# Adafruit_PowerBoost_1000C_Rev_B.net
KiCad netlist of a schematic drawn in EAGLE
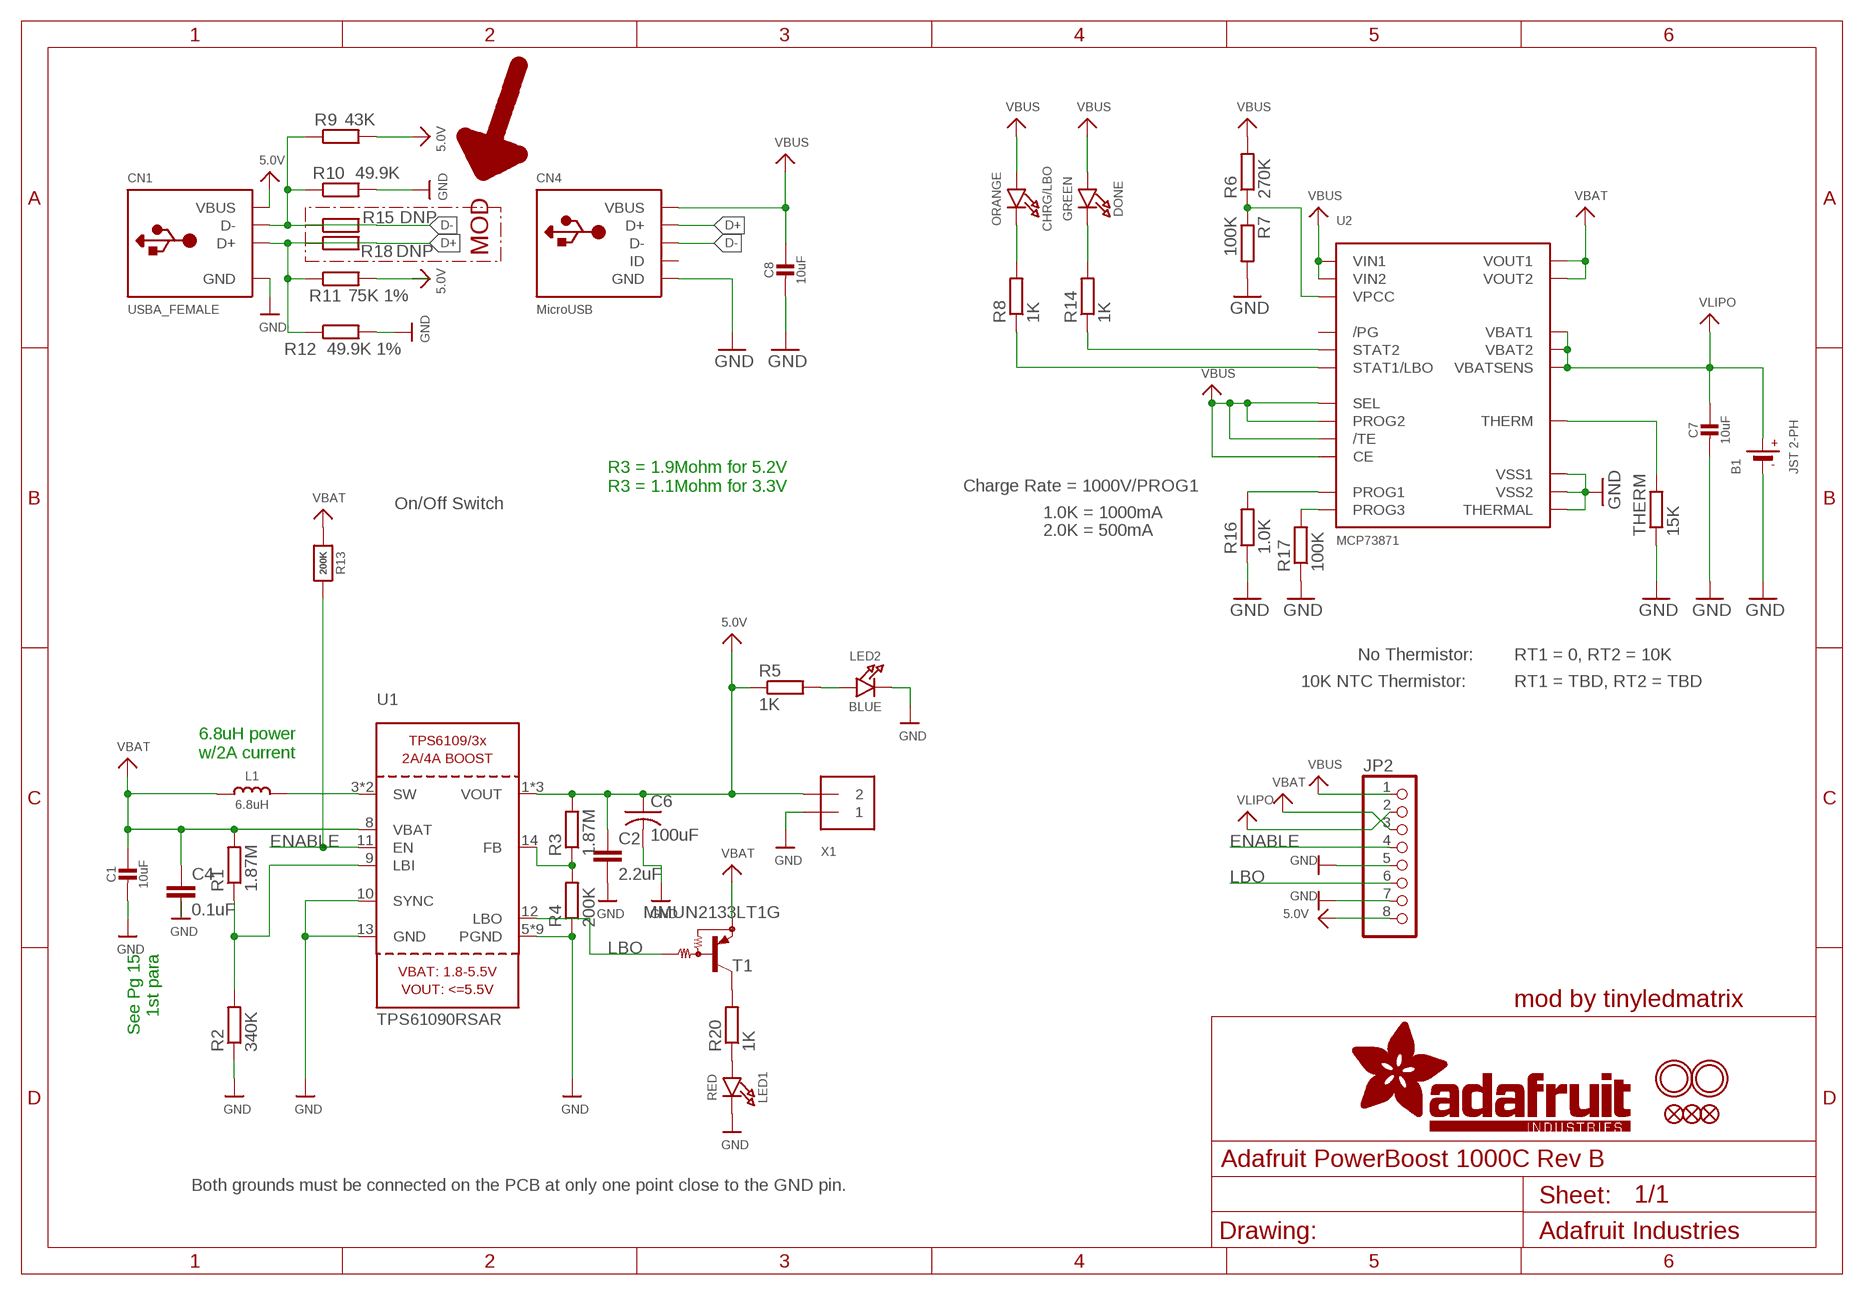
[diagram p0: schematic, sheet 1]

(export (version "E")
  (design (tool "Eeschema 10.0.6"))
  (components
    (comp (ref "B1")
      (value "JST 2-PH")
      (footprint "eagle-import:JSTPH2")
      (libsource (lib "eagle-import") (part "BATTERY"))
    )
    (comp (ref "C1")
      (value "10uF")
      (footprint "eagle-import:0805-NO")
      (libsource (lib "eagle-import") (part "CAP_CERAMIC0805-NOOUTLINE"))
    )
    (comp (ref "C2")
      (value "2.2uF")
      (footprint "eagle-import:C0603-VISHAY")
      (libsource (lib "eagle-import") (part "C-EUC0603-VISHAY"))
    )
    (comp (ref "C4")
      (value "0.1uF")
      (footprint "eagle-import:C0603-VISHAY")
      (libsource (lib "eagle-import") (part "C-EUC0603-VISHAY"))
    )
    (comp (ref "C6")
      (value "100uF")
      (footprint "eagle-import:C1210")
      (libsource (lib "eagle-import") (part "C-USC1210"))
    )
    (comp (ref "C7")
      (value "10uF")
      (footprint "eagle-import:0805-NO")
      (libsource (lib "eagle-import") (part "CAP_CERAMIC0805-NOOUTLINE"))
    )
    (comp (ref "C8")
      (value "10uF")
      (footprint "eagle-import:0805-NO")
      (libsource (lib "eagle-import") (part "CAP_CERAMIC0805-NOOUTLINE"))
    )
    (comp (ref "CHRG/LBO")
      (value "ORANGE")
      (footprint "eagle-import:CHIPLED_0603_NOOUTLINE")
      (libsource (lib "eagle-import") (part "LED0603_NOOUTLINE"))
    )
    (comp (ref "CN1")
      (value "USBA_FEMALE")
      (footprint "eagle-import:USB_HOST-PTH")
      (libsource (lib "eagle-import") (part "USB_TYPEAPTHFML"))
    )
    (comp (ref "CN4")
      (value "MicroUSB")
      (footprint "eagle-import:4UCONN_20329")
      (libsource (lib "eagle-import") (part "USBMICRO_20329"))
    )
    (comp (ref "DONE")
      (value "GREEN")
      (footprint "eagle-import:CHIPLED_0603_NOOUTLINE")
      (libsource (lib "eagle-import") (part "LED0603_NOOUTLINE"))
    )
    (comp (ref "FID1")
      (value "FIDUCIAL\"\"")
      (footprint "eagle-import:FIDUCIAL_1MM")
      (fields (field (name "BOM") "EXCLUDE"))
      (libsource (lib "eagle-import") (part "FIDUCIAL{dblquote}{dblquote}"))
    )
    (comp (ref "FID2")
      (value "FIDUCIAL\"\"")
      (footprint "eagle-import:FIDUCIAL_1MM")
      (libsource (lib "eagle-import") (part "FIDUCIAL{dblquote}{dblquote}"))
    )
    (comp (ref "FID3")
      (value "FIDUCIAL\"\"")
      (footprint "eagle-import:FIDUCIAL_1MM")
      (fields (field (name "BOM") "EXCLUDE"))
      (libsource (lib "eagle-import") (part "FIDUCIAL{dblquote}{dblquote}"))
    )
    (comp (ref "JP2")
      (value "HEADER-1X8ROUND")
      (footprint "eagle-import:1X08_ROUND")
      (libsource (lib "eagle-import") (part "HEADER-1X8ROUND"))
    )
    (comp (ref "L1")
      (value "6.8uH")
      (footprint "eagle-import:INDUCTOR_5X5MM_TDK_VLC5045")
      (libsource (lib "eagle-import") (part "INDUCTORTDK_VLC5045"))
    )
    (comp (ref "LED1")
      (value "RED")
      (footprint "eagle-import:CHIPLED_0603_NOOUTLINE")
      (libsource (lib "eagle-import") (part "LED0603_NOOUTLINE"))
    )
    (comp (ref "LED2")
      (value "BLUE")
      (footprint "eagle-import:CHIPLED_0603_NOOUTLINE")
      (libsource (lib "eagle-import") (part "LED0603_NOOUTLINE"))
    )
    (comp (ref "R1")
      (value "1.87M")
      (footprint "eagle-import:ADAFRUIT_R0603-VISHAY")
      (libsource (lib "eagle-import") (part "R-EU_R0603-VISHAY"))
    )
    (comp (ref "R2")
      (value "340K")
      (footprint "eagle-import:ADAFRUIT_R0603-VISHAY")
      (libsource (lib "eagle-import") (part "R-EU_R0603-VISHAY"))
    )
    (comp (ref "R3")
      (value "1.87M")
      (footprint "eagle-import:ADAFRUIT_R0603-VISHAY")
      (libsource (lib "eagle-import") (part "R-EU_R0603-VISHAY"))
    )
    (comp (ref "R4")
      (value "200K")
      (footprint "eagle-import:ADAFRUIT_R0603-VISHAY")
      (libsource (lib "eagle-import") (part "R-EU_R0603-VISHAY"))
    )
    (comp (ref "R5")
      (value "1K")
      (footprint "eagle-import:ADAFRUIT_R0603-VISHAY")
      (libsource (lib "eagle-import") (part "R-EU_R0603-VISHAY"))
    )
    (comp (ref "R6")
      (value "270K")
      (footprint "eagle-import:ADAFRUIT_R0603-VISHAY")
      (libsource (lib "eagle-import") (part "R-EU_R0603-VISHAY"))
    )
    (comp (ref "R7")
      (value "100K")
      (footprint "eagle-import:ADAFRUIT_R0603-VISHAY")
      (libsource (lib "eagle-import") (part "R-EU_R0603-VISHAY"))
    )
    (comp (ref "R8")
      (value "1K")
      (footprint "eagle-import:ADAFRUIT_R0603-VISHAY")
      (libsource (lib "eagle-import") (part "R-EU_R0603-VISHAY"))
    )
    (comp (ref "R9")
      (value "43K")
      (footprint "eagle-import:ADAFRUIT_R0603-VISHAY")
      (libsource (lib "eagle-import") (part "R-EU_R0603-VISHAY"))
    )
    (comp (ref "R10")
      (value "49.9K")
      (footprint "eagle-import:ADAFRUIT_R0603-VISHAY")
      (libsource (lib "eagle-import") (part "R-EU_R0603-VISHAY"))
    )
    (comp (ref "R11")
      (value "75K 1%")
      (footprint "eagle-import:ADAFRUIT_R0603-VISHAY")
      (libsource (lib "eagle-import") (part "R-EU_R0603-VISHAY"))
    )
    (comp (ref "R12")
      (value "49.9K 1%")
      (footprint "eagle-import:ADAFRUIT_R0603-VISHAY")
      (libsource (lib "eagle-import") (part "R-EU_R0603-VISHAY"))
    )
    (comp (ref "R13")
      (value "200K")
      (footprint "eagle-import:0805-NO")
      (libsource (lib "eagle-import") (part "RESISTOR0805_NOOUTLINE"))
    )
    (comp (ref "R14")
      (value "1K")
      (footprint "eagle-import:ADAFRUIT_R0603-VISHAY")
      (libsource (lib "eagle-import") (part "R-EU_R0603-VISHAY"))
    )
    (comp (ref "R15")
      (value "DNP")
      (footprint "eagle-import:ADAFRUIT_R0603-VISHAY")
      (libsource (lib "eagle-import") (part "R-EU_R0603-VISHAY"))
    )
    (comp (ref "R16")
      (value "1.0K")
      (footprint "eagle-import:ADAFRUIT_R0603-VISHAY")
      (libsource (lib "eagle-import") (part "R-EU_R0603-VISHAY"))
    )
    (comp (ref "R17")
      (value "100K")
      (footprint "eagle-import:ADAFRUIT_R0603-VISHAY")
      (libsource (lib "eagle-import") (part "R-EU_R0603-VISHAY"))
    )
    (comp (ref "R18")
      (value "DNP")
      (footprint "eagle-import:ADAFRUIT_R0603-VISHAY")
      (libsource (lib "eagle-import") (part "R-EU_R0603-VISHAY"))
    )
    (comp (ref "R20")
      (value "1K")
      (footprint "eagle-import:ADAFRUIT_R0603-VISHAY")
      (libsource (lib "eagle-import") (part "R-EU_R0603-VISHAY"))
    )
    (comp (ref "T1")
      (value "MMUN2133LT1G")
      (footprint "eagle-import:SC59-BEC")
      (libsource (lib "eagle-import") (part "-PNP_DRIVER-SC59-BECMUN2114T1"))
    )
    (comp (ref "THERM")
      (value "15K")
      (footprint "eagle-import:ADAFRUIT_R0603-VISHAY")
      (libsource (lib "eagle-import") (part "R-EU_R0603-VISHAY"))
    )
    (comp (ref "U$10")
      (value "MOUNTINGHOLE2.5")
      (footprint "eagle-import:MOUNTINGHOLE_2.5_PLATED")
      (libsource (lib "eagle-import") (part "MOUNTINGHOLE2.5"))
    )
    (comp (ref "U$11")
      (value "MOUNTINGHOLE2.5")
      (footprint "eagle-import:MOUNTINGHOLE_2.5_PLATED")
      (libsource (lib "eagle-import") (part "MOUNTINGHOLE2.5"))
    )
    (comp (ref "U1")
      (value "TPS61090RSAR")
      (footprint "eagle-import:PVQFN-16")
      (libsource (lib "eagle-import") (part "VREG_TPS6103X"))
    )
    (comp (ref "U2")
      (value "MCP73871")
      (footprint "eagle-import:QFN20_4MM")
      (libsource (lib "eagle-import") (part "MCP73871"))
    )
    (comp (ref "X1")
      (value "TERMBLOCK_1X2")
      (footprint "eagle-import:TERMBLOCK_1X2-3.5MM")
      (libsource (lib "eagle-import") (part "TERMBLOCK_1X2"))
    )
  )
  (nets
    (net (code "1") (name "/ENABLE") (class "Default")
      (node (ref "JP2") (pin "4") (pinfunction "4_4") (pintype "passive"))
      (node (ref "R13") (pin "2") (pinfunction "2_2") (pintype "passive"))
      (node (ref "U1") (pin "11") (pinfunction "EN_11") (pintype "input"))
    )
    (net (code "2") (name "/LBO") (class "Default")
      (node (ref "JP2") (pin "6") (pinfunction "6_6") (pintype "passive"))
      (node (ref "T1") (pin "B") (pinfunction "B_B") (pintype "passive"))
      (node (ref "U1") (pin "12") (pinfunction "LBO_12") (pintype "output"))
    )
    (net (code "3") (name "5.0V") (class "Default")
      (node (ref "C2") (pin "1") (pinfunction "1_1") (pintype "passive"))
      (node (ref "C6") (pin "1") (pinfunction "1_1") (pintype "passive"))
      (node (ref "CN1") (pin "VBUS") (pinfunction "VBUS_VBUS") (pintype "power_in"))
      (node (ref "JP2") (pin "8") (pinfunction "8_8") (pintype "passive"))
      (node (ref "R11") (pin "2") (pinfunction "2_2") (pintype "passive"))
      (node (ref "R3") (pin "2") (pinfunction "2_2") (pintype "passive"))
      (node (ref "R5") (pin "1") (pinfunction "1_1") (pintype "passive"))
      (node (ref "R9") (pin "2") (pinfunction "2_2") (pintype "passive"))
      (node (ref "U1") (pin "1") (pinfunction "VOUT_1") (pintype "power_in"))
      (node (ref "U1") (pin "15") (pinfunction "VOUT_15") (pintype "power_in"))
      (node (ref "U1") (pin "16") (pinfunction "VOUT_16") (pintype "power_in"))
      (node (ref "X1") (pin "2") (pinfunction "2_2") (pintype "passive"))
    )
    (net (code "4") (name "D+") (class "Default")
      (node (ref "CN1") (pin "D+") (pinfunction "D+_D+") (pintype "bidirectional"))
      (node (ref "CN4") (pin "D+") (pinfunction "D+_D+") (pintype "bidirectional"))
      (node (ref "R11") (pin "1") (pinfunction "1_1") (pintype "passive"))
      (node (ref "R12") (pin "1") (pinfunction "1_1") (pintype "passive"))
      (node (ref "R18") (pin "1") (pinfunction "1_1") (pintype "passive"))
      (node (ref "R18") (pin "2") (pinfunction "2_2") (pintype "passive"))
    )
    (net (code "5") (name "D-") (class "Default")
      (node (ref "CN1") (pin "D-") (pinfunction "D-_D-") (pintype "bidirectional"))
      (node (ref "CN4") (pin "D-") (pinfunction "D-_D-") (pintype "bidirectional"))
      (node (ref "R10") (pin "1") (pinfunction "1_1") (pintype "passive"))
      (node (ref "R15") (pin "1") (pinfunction "1_1") (pintype "passive"))
      (node (ref "R15") (pin "2") (pinfunction "2_2") (pintype "passive"))
      (node (ref "R9") (pin "1") (pinfunction "1_1") (pintype "passive"))
    )
    (net (code "6") (name "GND") (class "Default")
      (node (ref "B1") (pin "1") (pinfunction "-_1") (pintype "passive"))
      (node (ref "C1") (pin "2") (pinfunction "2_2") (pintype "passive"))
      (node (ref "C2") (pin "2") (pinfunction "2_2") (pintype "passive"))
      (node (ref "C4") (pin "2") (pinfunction "2_2") (pintype "passive"))
      (node (ref "C6") (pin "2") (pinfunction "2_2") (pintype "passive"))
      (node (ref "C7") (pin "2") (pinfunction "2_2") (pintype "passive"))
      (node (ref "C8") (pin "2") (pinfunction "2_2") (pintype "passive"))
      (node (ref "CN1") (pin "GND") (pinfunction "GND_GND") (pintype "power_in"))
      (node (ref "CN4") (pin "BASE@1") (pinfunction "GND_BASE@1") (pintype "power_in"))
      (node (ref "CN4") (pin "BASE@2") (pinfunction "GND_BASE@2") (pintype "power_in"))
      (node (ref "CN4") (pin "GND") (pinfunction "GND_GND") (pintype "power_in"))
      (node (ref "CN4") (pin "SPRT@1") (pinfunction "GND_SPRT@1") (pintype "power_in"))
      (node (ref "CN4") (pin "SPRT@2") (pinfunction "GND_SPRT@2") (pintype "power_in"))
      (node (ref "CN4") (pin "SPRT@3") (pinfunction "GND_SPRT@3") (pintype "power_in"))
      (node (ref "CN4") (pin "SPRT@4") (pinfunction "GND_SPRT@4") (pintype "power_in"))
      (node (ref "JP2") (pin "5") (pinfunction "5_5") (pintype "passive"))
      (node (ref "JP2") (pin "7") (pinfunction "7_7") (pintype "passive"))
      (node (ref "LED1") (pin "C") (pinfunction "C_C") (pintype "passive"))
      (node (ref "LED2") (pin "C") (pinfunction "C_C") (pintype "passive"))
      (node (ref "R10") (pin "2") (pinfunction "2_2") (pintype "passive"))
      (node (ref "R12") (pin "2") (pinfunction "2_2") (pintype "passive"))
      (node (ref "R16") (pin "1") (pinfunction "1_1") (pintype "passive"))
      (node (ref "R17") (pin "1") (pinfunction "1_1") (pintype "passive"))
      (node (ref "R2") (pin "1") (pinfunction "1_1") (pintype "passive"))
      (node (ref "R4") (pin "1") (pinfunction "1_1") (pintype "passive"))
      (node (ref "R7") (pin "2") (pinfunction "2_2") (pintype "passive"))
      (node (ref "THERM") (pin "1") (pinfunction "1_1") (pintype "passive"))
      (node (ref "U1") (pin "10") (pinfunction "SYNC_10") (pintype "input"))
      (node (ref "U1") (pin "13") (pinfunction "GND_13") (pintype "power_in"))
      (node (ref "U1") (pin "5") (pinfunction "PGND_5") (pintype "power_in"))
      (node (ref "U1") (pin "6") (pinfunction "PGND_6") (pintype "power_in"))
      (node (ref "U1") (pin "7") (pinfunction "PGND_7") (pintype "power_in"))
      (node (ref "U1") (pin "P$18") (pinfunction "PGND_P$18") (pintype "power_in"))
      (node (ref "U1") (pin "P$19") (pinfunction "PGND_P$19") (pintype "power_in"))
      (node (ref "U1") (pin "P$20") (pinfunction "PGND_P$20") (pintype "power_in"))
      (node (ref "U1") (pin "P$21") (pinfunction "PGND_P$21") (pintype "power_in"))
      (node (ref "U1") (pin "P$22") (pinfunction "PGND_P$22") (pintype "power_in"))
      (node (ref "U1") (pin "THERMAL") (pinfunction "PGND_THERMAL") (pintype "power_in"))
      (node (ref "U2") (pin "P$10") (pinfunction "VSS1_P$10") (pintype "bidirectional"))
      (node (ref "U2") (pin "P$11") (pinfunction "VSS2_P$11") (pintype "bidirectional"))
      (node (ref "U2") (pin "P$21") (pinfunction "THERMAL_P$21") (pintype "bidirectional"))
      (node (ref "X1") (pin "1") (pinfunction "1_1") (pintype "passive"))
    )
    (net (code "7") (name "Net-(CHRG/LBO-PadC)") (class "Default")
      (node (ref "CHRG/LBO") (pin "C") (pinfunction "C_C") (pintype "passive"))
      (node (ref "R8") (pin "2") (pinfunction "2_2") (pintype "passive"))
    )
    (net (code "8") (name "Net-(DONE-PadC)") (class "Default")
      (node (ref "DONE") (pin "C") (pinfunction "C_C") (pintype "passive"))
      (node (ref "R14") (pin "2") (pinfunction "2_2") (pintype "passive"))
    )
    (net (code "9") (name "Net-(L1-2)") (class "Default")
      (node (ref "L1") (pin "P$2") (pinfunction "2_P$2") (pintype "passive"))
      (node (ref "U1") (pin "3") (pinfunction "SW_3") (pintype "input"))
      (node (ref "U1") (pin "4") (pinfunction "SW_4") (pintype "input"))
    )
    (net (code "10") (name "Net-(LED1-PadA)") (class "Default")
      (node (ref "LED1") (pin "A") (pinfunction "A_A") (pintype "passive"))
      (node (ref "R20") (pin "1") (pinfunction "1_1") (pintype "passive"))
    )
    (net (code "11") (name "Net-(LED2-PadA)") (class "Default")
      (node (ref "LED2") (pin "A") (pinfunction "A_A") (pintype "passive"))
      (node (ref "R5") (pin "2") (pinfunction "2_2") (pintype "passive"))
    )
    (net (code "12") (name "Net-(R20-Pad2)") (class "Default")
      (node (ref "R20") (pin "2") (pinfunction "2_2") (pintype "passive"))
      (node (ref "T1") (pin "C") (pinfunction "C_C") (pintype "passive"))
    )
    (net (code "13") (name "Net-(U1-FB)") (class "Default")
      (node (ref "R3") (pin "1") (pinfunction "1_1") (pintype "passive"))
      (node (ref "R4") (pin "2") (pinfunction "2_2") (pintype "passive"))
      (node (ref "U1") (pin "14") (pinfunction "FB_14") (pintype "input"))
    )
    (net (code "14") (name "Net-(U1-LBI)") (class "Default")
      (node (ref "R1") (pin "1") (pinfunction "1_1") (pintype "passive"))
      (node (ref "R2") (pin "2") (pinfunction "2_2") (pintype "passive"))
      (node (ref "U1") (pin "9") (pinfunction "LBI_9") (pintype "input"))
    )
    (net (code "15") (name "Net-(U2-PROG1)") (class "Default")
      (node (ref "R16") (pin "2") (pinfunction "2_2") (pintype "passive"))
      (node (ref "U2") (pin "P$13") (pinfunction "PROG1_P$13") (pintype "bidirectional"))
    )
    (net (code "16") (name "Net-(U2-PROG3)") (class "Default")
      (node (ref "R17") (pin "2") (pinfunction "2_2") (pintype "passive"))
      (node (ref "U2") (pin "P$12") (pinfunction "PROG3_P$12") (pintype "bidirectional"))
    )
    (net (code "17") (name "Net-(U2-STAT1{slash}LBO)") (class "Default")
      (node (ref "R8") (pin "1") (pinfunction "1_1") (pintype "passive"))
      (node (ref "U2") (pin "P$8") (pinfunction "STAT1/LBO_P$8") (pintype "bidirectional"))
    )
    (net (code "18") (name "Net-(U2-STAT2)") (class "Default")
      (node (ref "R14") (pin "1") (pinfunction "1_1") (pintype "passive"))
      (node (ref "U2") (pin "P$7") (pinfunction "STAT2_P$7") (pintype "bidirectional"))
    )
    (net (code "19") (name "Net-(U2-THERM)") (class "Default")
      (node (ref "THERM") (pin "2") (pinfunction "2_2") (pintype "passive"))
      (node (ref "U2") (pin "P$5") (pinfunction "THERM_P$5") (pintype "bidirectional"))
    )
    (net (code "20") (name "Net-(U2-VPCC)") (class "Default")
      (node (ref "R6") (pin "1") (pinfunction "1_1") (pintype "passive"))
      (node (ref "R7") (pin "1") (pinfunction "1_1") (pintype "passive"))
      (node (ref "U2") (pin "P$2") (pinfunction "VPCC_P$2") (pintype "bidirectional"))
    )
    (net (code "21") (name "VBAT") (class "Default")
      (node (ref "C1") (pin "1") (pinfunction "1_1") (pintype "passive"))
      (node (ref "C4") (pin "1") (pinfunction "1_1") (pintype "passive"))
      (node (ref "JP2") (pin "3") (pinfunction "3_3") (pintype "passive"))
      (node (ref "L1") (pin "P$1") (pinfunction "1_P$1") (pintype "passive"))
      (node (ref "R1") (pin "2") (pinfunction "2_2") (pintype "passive"))
      (node (ref "R13") (pin "1") (pinfunction "1_1") (pintype "passive"))
      (node (ref "T1") (pin "E") (pinfunction "E_E") (pintype "passive"))
      (node (ref "U1") (pin "8") (pinfunction "VBAT_8") (pintype "input"))
      (node (ref "U2") (pin "P$1") (pinfunction "VOUT1_P$1") (pintype "bidirectional"))
      (node (ref "U2") (pin "P$20") (pinfunction "VOUT2_P$20") (pintype "bidirectional"))
    )
    (net (code "22") (name "VBUS") (class "Default")
      (node (ref "C8") (pin "1") (pinfunction "1_1") (pintype "passive"))
      (node (ref "CHRG/LBO") (pin "A") (pinfunction "A_A") (pintype "passive"))
      (node (ref "CN4") (pin "VBUS") (pinfunction "VBUS_VBUS") (pintype "power_in"))
      (node (ref "DONE") (pin "A") (pinfunction "A_A") (pintype "passive"))
      (node (ref "JP2") (pin "1") (pinfunction "1_1") (pintype "passive"))
      (node (ref "R6") (pin "2") (pinfunction "2_2") (pintype "passive"))
      (node (ref "U2") (pin "P$17") (pinfunction "CE_P$17") (pintype "bidirectional"))
      (node (ref "U2") (pin "P$18") (pinfunction "VIN1_P$18") (pintype "bidirectional"))
      (node (ref "U2") (pin "P$19") (pinfunction "VIN2_P$19") (pintype "bidirectional"))
      (node (ref "U2") (pin "P$3") (pinfunction "SEL_P$3") (pintype "bidirectional"))
      (node (ref "U2") (pin "P$4") (pinfunction "PROG2_P$4") (pintype "bidirectional"))
      (node (ref "U2") (pin "P$9") (pinfunction "/TE_P$9") (pintype "bidirectional"))
    )
    (net (code "23") (name "VLIPO") (class "Default")
      (node (ref "B1") (pin "2") (pinfunction "+_2") (pintype "passive"))
      (node (ref "C7") (pin "1") (pinfunction "1_1") (pintype "passive"))
      (node (ref "JP2") (pin "2") (pinfunction "2_2") (pintype "passive"))
      (node (ref "U2") (pin "P$14") (pinfunction "VBAT1_P$14") (pintype "bidirectional"))
      (node (ref "U2") (pin "P$15") (pinfunction "VBAT2_P$15") (pintype "bidirectional"))
      (node (ref "U2") (pin "P$16") (pinfunction "VBATSENS_P$16") (pintype "bidirectional"))
    )
    (net (code "24") (name "unconnected-(CN4-PadID)") (class "Default")
      (node (ref "CN4") (pin "ID") (pinfunction "ID_ID") (pintype "bidirectional"))
    )
    (net (code "25") (name "unconnected-(U2-{slash}PG-PadP$6)") (class "Default")
      (node (ref "U2") (pin "P$6") (pinfunction "/PG_P$6") (pintype "bidirectional"))
    )
  )
)
